# Hub.net
KiCad netlist of a schematic drawn in EAGLE
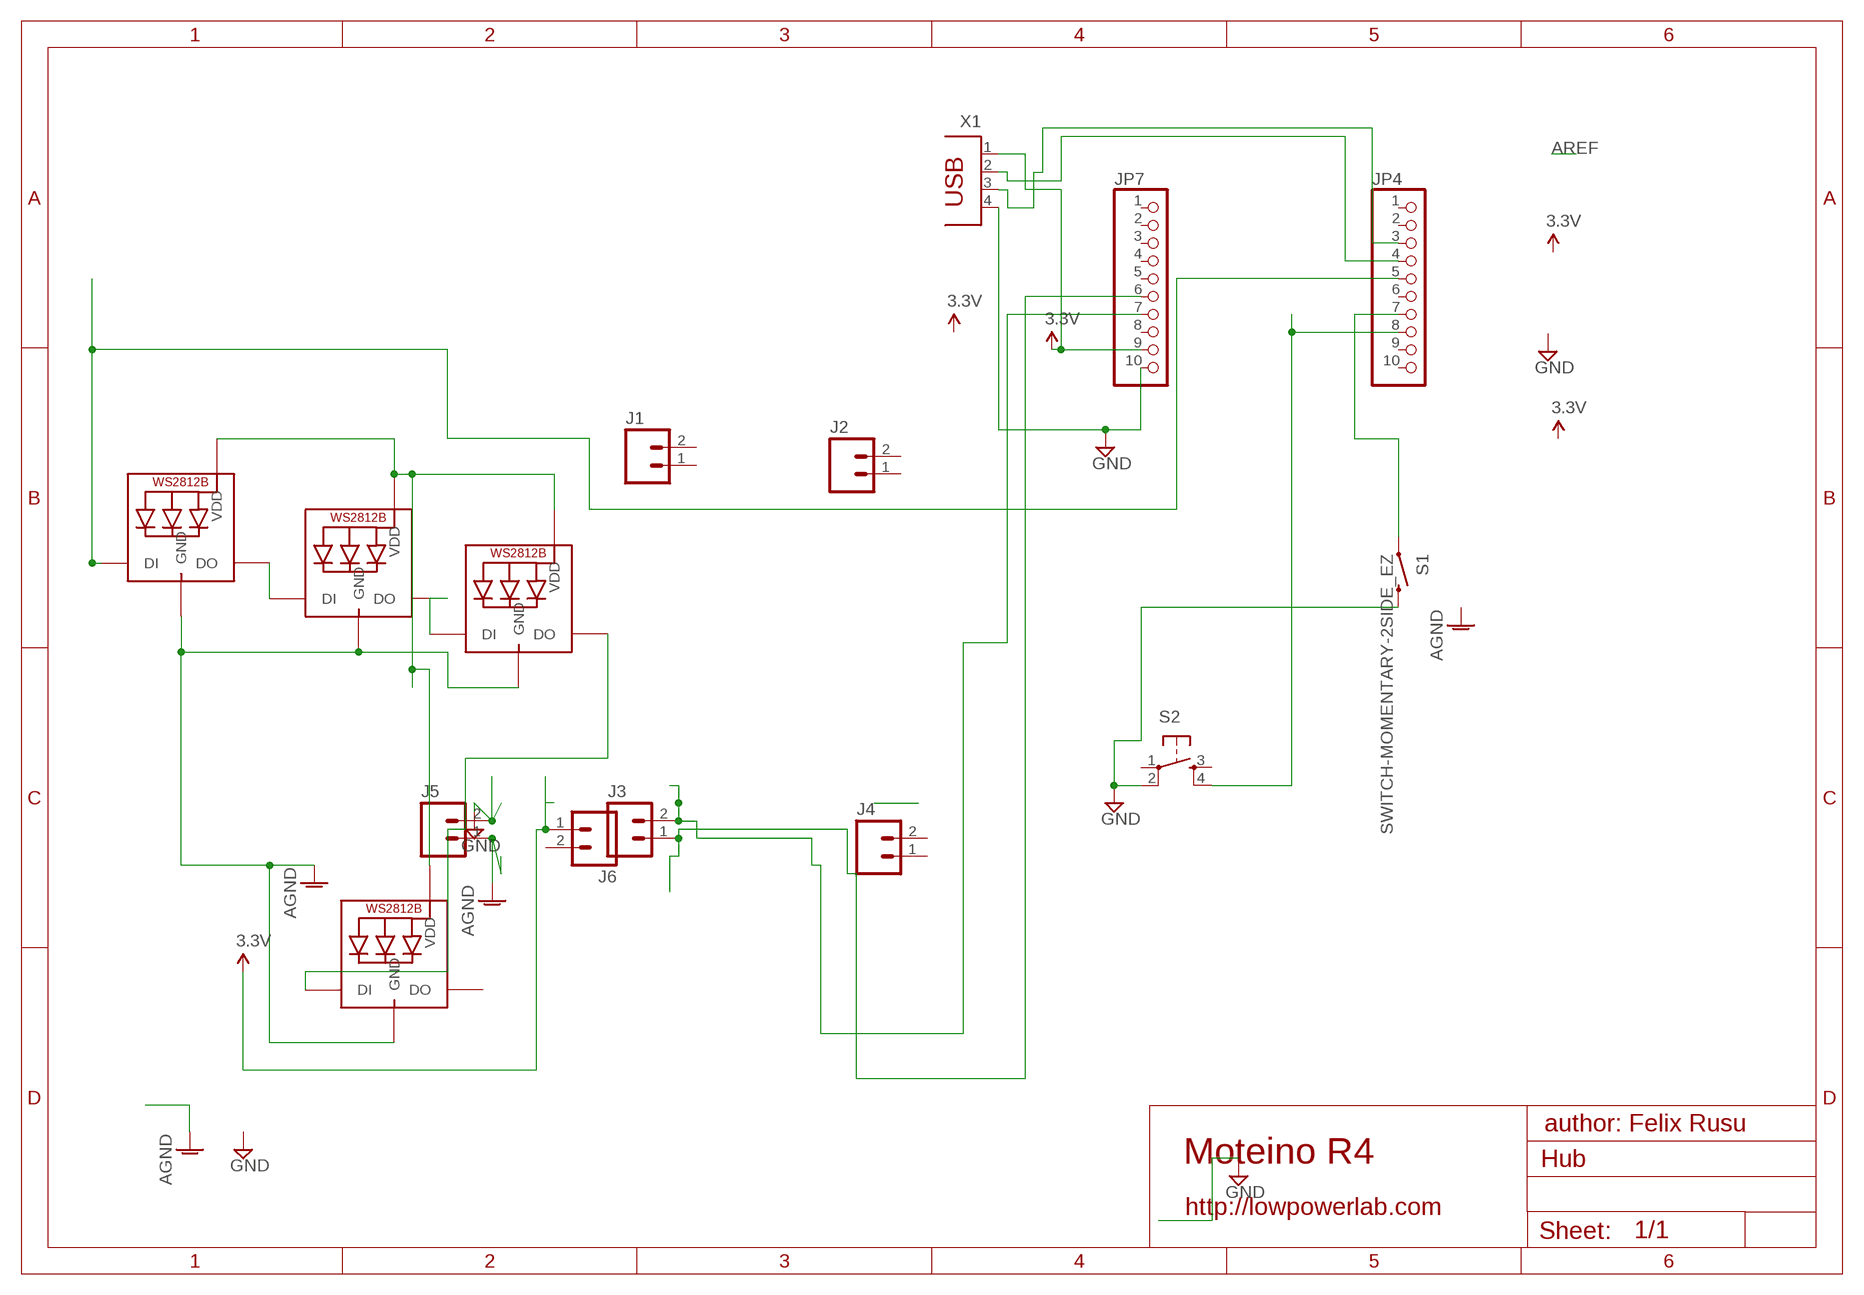
[diagram p0: schematic, sheet 1]

(export (version "E")
  (design (tool "Eeschema 10.0.6"))
  (components
    (comp (ref "J1")
      (value "M02PTH")
      (footprint "eagle-import:1X02")
      (libsource (lib "eagle-import") (part "M02PTH"))
    )
    (comp (ref "J2")
      (value "M02PTH")
      (footprint "eagle-import:1X02")
      (libsource (lib "eagle-import") (part "M02PTH"))
    )
    (comp (ref "J3")
      (value "M02PTH")
      (footprint "eagle-import:1X02")
      (libsource (lib "eagle-import") (part "M02PTH"))
    )
    (comp (ref "J4")
      (value "M02PTH")
      (footprint "eagle-import:1X02")
      (libsource (lib "eagle-import") (part "M02PTH"))
    )
    (comp (ref "J5")
      (value "M02PTH")
      (footprint "eagle-import:1X02")
      (libsource (lib "eagle-import") (part "M02PTH"))
    )
    (comp (ref "J6")
      (value "M02PTH")
      (footprint "eagle-import:1X02")
      (libsource (lib "eagle-import") (part "M02PTH"))
    )
    (comp (ref "JP4")
      (value "PINHD-1X10")
      (footprint "eagle-import:1X10")
      (libsource (lib "eagle-import") (part "PINHD-1X10"))
    )
    (comp (ref "JP7")
      (value "PINHD-1X10")
      (footprint "eagle-import:1X10")
      (libsource (lib "eagle-import") (part "PINHD-1X10"))
    )
    (comp (ref "LED1")
      (value "WS2812B5050")
      (footprint "eagle-import:WS2812B")
      (libsource (lib "eagle-import") (part "WS2812B5050"))
    )
    (comp (ref "LED2")
      (value "WS2812B5050")
      (footprint "eagle-import:WS2812B")
      (libsource (lib "eagle-import") (part "WS2812B5050"))
    )
    (comp (ref "LED3")
      (value "WS2812B5050")
      (footprint "eagle-import:WS2812B")
      (libsource (lib "eagle-import") (part "WS2812B5050"))
    )
    (comp (ref "LED5")
      (value "WS2812B5050")
      (footprint "eagle-import:WS2812B")
      (libsource (lib "eagle-import") (part "WS2812B5050"))
    )
    (comp (ref "S1")
      (value "SWITCH-MOMENTARY-2SIDE_EZ")
      (footprint "eagle-import:TACTILE-PTH-SIDEEZ")
      (libsource (lib "eagle-import") (part "SWITCH-MOMENTARY-2SIDE_EZ"))
    )
    (comp (ref "S2")
      (value "TAC_SWITCHPTH")
      (footprint "eagle-import:TACTILE-PTH")
      (libsource (lib "eagle-import") (part "TAC_SWITCHPTH"))
    )
    (comp (ref "X1")
      (value "PN87520")
      (footprint "eagle-import:PN87520")
      (libsource (lib "eagle-import") (part "PN87520"))
    )
  )
  (nets
    (net (code "2") (name "3.3V") (class "Default")
      (node (ref "J6") (pin "1") (pinfunction "1_1") (pintype "passive"))
      (node (ref "JP7") (pin "9") (pinfunction "9_9") (pintype "passive"))
      (node (ref "X1") (pin "1") (pinfunction "1_1") (pintype "passive"))
    )
    (net (code "3") (name "AGND") (class "Default")
      (node (ref "J5") (pin "1") (pinfunction "1_1") (pintype "passive"))
      (node (ref "LED1") (pin "3-GND") (pinfunction "GND_3-GND") (pintype "power_in"))
      (node (ref "LED2") (pin "3-GND") (pinfunction "GND_3-GND") (pintype "power_in"))
      (node (ref "LED3") (pin "3-GND") (pinfunction "GND_3-GND") (pintype "power_in"))
      (node (ref "LED5") (pin "3-GND") (pinfunction "GND_3-GND") (pintype "power_in"))
    )
    (net (code "4") (name "GND") (class "Default")
      (node (ref "J5") (pin "2") (pinfunction "2_2") (pintype "passive"))
      (node (ref "JP7") (pin "10") (pinfunction "10_10") (pintype "passive"))
      (node (ref "S1") (pin "2") (pinfunction "2_2") (pintype "passive"))
      (node (ref "S2") (pin "2") (pinfunction "2_2") (pintype "passive"))
      (node (ref "X1") (pin "4") (pinfunction "4_4") (pintype "passive"))
    )
    (net (code "5") (name "Net-(J3-Pad1)") (class "Default")
      (node (ref "J3") (pin "1") (pinfunction "1_1") (pintype "passive"))
      (node (ref "JP7") (pin "6") (pinfunction "6_6") (pintype "passive"))
    )
    (net (code "6") (name "Net-(J3-Pad2)") (class "Default")
      (node (ref "J3") (pin "2") (pinfunction "2_2") (pintype "passive"))
      (node (ref "JP7") (pin "7") (pinfunction "7_7") (pintype "passive"))
    )
    (net (code "7") (name "Net-(JP4-Pad3)") (class "Default")
      (node (ref "JP4") (pin "3") (pinfunction "3_3") (pintype "passive"))
      (node (ref "X1") (pin "3") (pinfunction "3_3") (pintype "passive"))
    )
    (net (code "8") (name "Net-(JP4-Pad4)") (class "Default")
      (node (ref "JP4") (pin "4") (pinfunction "4_4") (pintype "passive"))
      (node (ref "X1") (pin "2") (pinfunction "2_2") (pintype "passive"))
    )
    (net (code "9") (name "Net-(JP4-Pad7)") (class "Default")
      (node (ref "JP4") (pin "7") (pinfunction "7_7") (pintype "passive"))
      (node (ref "S1") (pin "1") (pinfunction "1_1") (pintype "passive"))
    )
    (net (code "10") (name "Net-(JP4-Pad8)") (class "Default")
      (node (ref "JP4") (pin "8") (pinfunction "8_8") (pintype "passive"))
      (node (ref "S2") (pin "4") (pinfunction "4_4") (pintype "passive"))
    )
    (net (code "11") (name "Net-(LED1-DI)") (class "Default")
      (node (ref "JP4") (pin "5") (pinfunction "5_5") (pintype "passive"))
      (node (ref "LED1") (pin "4-DIN") (pinfunction "DI_4-DIN") (pintype "input"))
    )
    (net (code "12") (name "Net-(LED1-DO)") (class "Default")
      (node (ref "LED1") (pin "2-DOUT") (pinfunction "DO_2-DOUT") (pintype "output"))
      (node (ref "LED2") (pin "4-DIN") (pinfunction "DI_4-DIN") (pintype "input"))
    )
    (net (code "13") (name "Net-(LED1-VDD)") (class "Default")
      (node (ref "LED1") (pin "1-VDD") (pinfunction "VDD_1-VDD") (pintype "power_in"))
      (node (ref "LED2") (pin "1-VDD") (pinfunction "VDD_1-VDD") (pintype "power_in"))
      (node (ref "LED3") (pin "1-VDD") (pinfunction "VDD_1-VDD") (pintype "power_in"))
      (node (ref "LED5") (pin "1-VDD") (pinfunction "VDD_1-VDD") (pintype "power_in"))
    )
    (net (code "14") (name "Net-(LED2-DO)") (class "Default")
      (node (ref "LED2") (pin "2-DOUT") (pinfunction "DO_2-DOUT") (pintype "output"))
      (node (ref "LED3") (pin "4-DIN") (pinfunction "DI_4-DIN") (pintype "input"))
    )
    (net (code "15") (name "Net-(LED3-DO)") (class "Default")
      (node (ref "LED3") (pin "2-DOUT") (pinfunction "DO_2-DOUT") (pintype "output"))
      (node (ref "LED5") (pin "4-DIN") (pinfunction "DI_4-DIN") (pintype "input"))
    )
    (net (code "16") (name "unconnected-(J1-Pad1)") (class "Default")
      (node (ref "J1") (pin "1") (pinfunction "1_1") (pintype "passive"))
    )
    (net (code "17") (name "unconnected-(J1-Pad2)") (class "Default")
      (node (ref "J1") (pin "2") (pinfunction "2_2") (pintype "passive"))
    )
    (net (code "18") (name "unconnected-(J2-Pad1)") (class "Default")
      (node (ref "J2") (pin "1") (pinfunction "1_1") (pintype "passive"))
    )
    (net (code "19") (name "unconnected-(J2-Pad2)") (class "Default")
      (node (ref "J2") (pin "2") (pinfunction "2_2") (pintype "passive"))
    )
    (net (code "20") (name "unconnected-(J4-Pad1)") (class "Default")
      (node (ref "J4") (pin "1") (pinfunction "1_1") (pintype "passive"))
    )
    (net (code "21") (name "unconnected-(J4-Pad2)") (class "Default")
      (node (ref "J4") (pin "2") (pinfunction "2_2") (pintype "passive"))
    )
    (net (code "22") (name "unconnected-(J6-Pad2)") (class "Default")
      (node (ref "J6") (pin "2") (pinfunction "2_2") (pintype "passive"))
    )
    (net (code "23") (name "unconnected-(JP4-Pad1)") (class "Default")
      (node (ref "JP4") (pin "1") (pinfunction "1_1") (pintype "passive"))
    )
    (net (code "24") (name "unconnected-(JP4-Pad2)") (class "Default")
      (node (ref "JP4") (pin "2") (pinfunction "2_2") (pintype "passive"))
    )
    (net (code "25") (name "unconnected-(JP4-Pad6)") (class "Default")
      (node (ref "JP4") (pin "6") (pinfunction "6_6") (pintype "passive"))
    )
    (net (code "26") (name "unconnected-(JP4-Pad9)") (class "Default")
      (node (ref "JP4") (pin "9") (pinfunction "9_9") (pintype "passive"))
    )
    (net (code "27") (name "unconnected-(JP4-Pad10)") (class "Default")
      (node (ref "JP4") (pin "10") (pinfunction "10_10") (pintype "passive"))
    )
    (net (code "28") (name "unconnected-(JP7-Pad1)") (class "Default")
      (node (ref "JP7") (pin "1") (pinfunction "1_1") (pintype "passive"))
    )
    (net (code "29") (name "unconnected-(JP7-Pad2)") (class "Default")
      (node (ref "JP7") (pin "2") (pinfunction "2_2") (pintype "passive"))
    )
    (net (code "30") (name "unconnected-(JP7-Pad3)") (class "Default")
      (node (ref "JP7") (pin "3") (pinfunction "3_3") (pintype "passive"))
    )
    (net (code "31") (name "unconnected-(JP7-Pad4)") (class "Default")
      (node (ref "JP7") (pin "4") (pinfunction "4_4") (pintype "passive"))
    )
    (net (code "32") (name "unconnected-(JP7-Pad5)") (class "Default")
      (node (ref "JP7") (pin "5") (pinfunction "5_5") (pintype "passive"))
    )
    (net (code "33") (name "unconnected-(JP7-Pad8)") (class "Default")
      (node (ref "JP7") (pin "8") (pinfunction "8_8") (pintype "passive"))
    )
    (net (code "34") (name "unconnected-(LED5-DO-Pad2-DOUT)") (class "Default")
      (node (ref "LED5") (pin "2-DOUT") (pinfunction "DO_2-DOUT") (pintype "output"))
    )
    (net (code "35") (name "unconnected-(S2-Pad1)") (class "Default")
      (node (ref "S2") (pin "1") (pinfunction "1_1") (pintype "passive"))
    )
    (net (code "36") (name "unconnected-(S2-Pad3)") (class "Default")
      (node (ref "S2") (pin "3") (pinfunction "3_3") (pintype "passive"))
    )
  )
)
